# RedBot.net
KiCad netlist of a schematic drawn in EAGLE
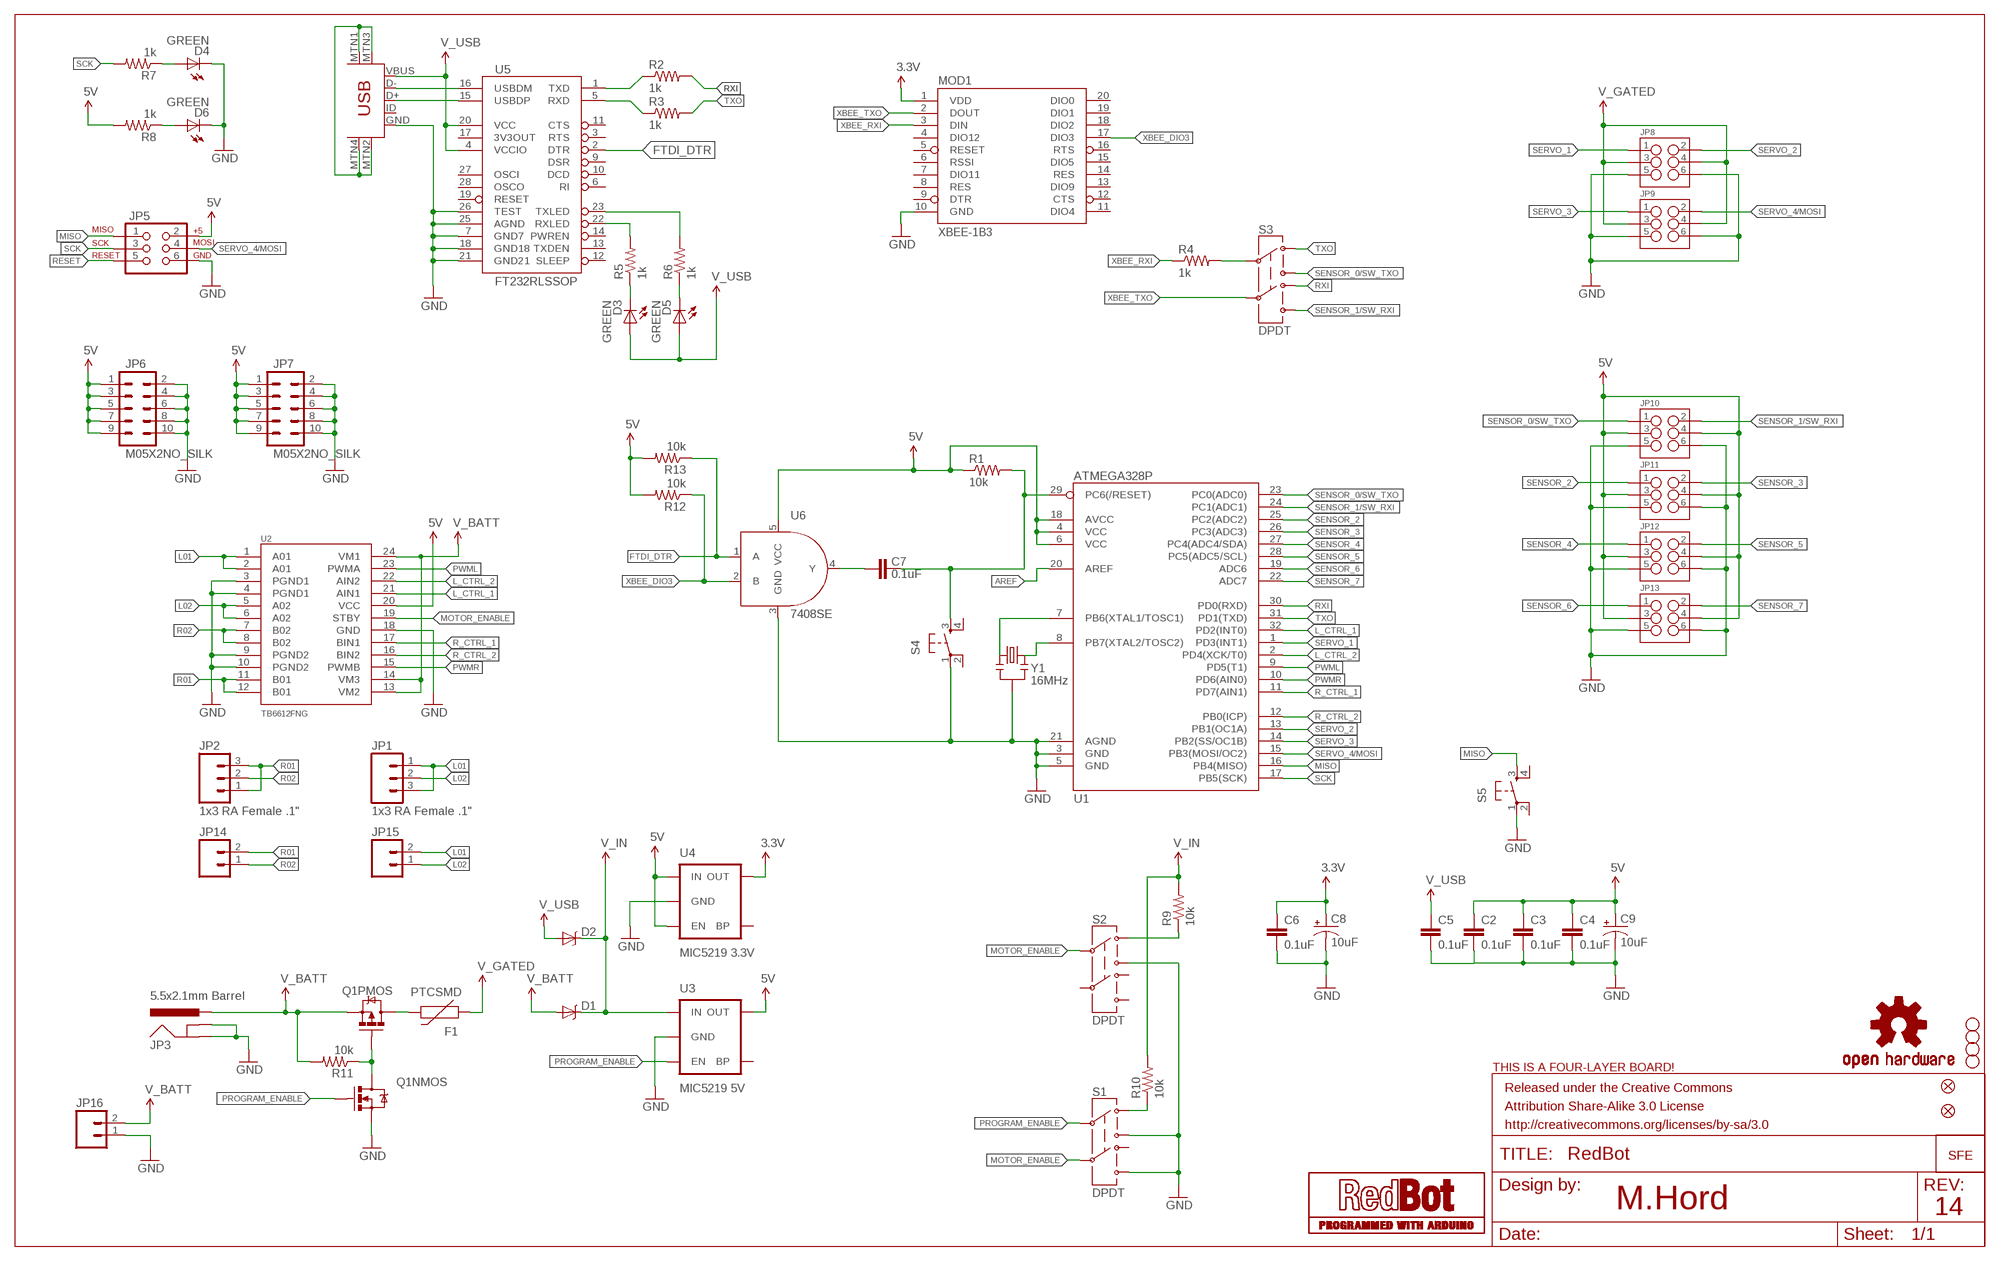
[diagram p0: schematic, sheet 1]

(export (version "E")
  (design (tool "Eeschema 10.0.6"))
  (components
    (comp (ref "C2")
      (value "0.1uF")
      (footprint "eagle-import:0603-CAP")
      (libsource (lib "eagle-import") (part "0.1UF-25V(+80/-20%)(0603)"))
    )
    (comp (ref "C3")
      (value "0.1uF")
      (footprint "eagle-import:0603-CAP")
      (libsource (lib "eagle-import") (part "0.1UF-25V(+80/-20%)(0603)"))
    )
    (comp (ref "C4")
      (value "0.1uF")
      (footprint "eagle-import:0603-CAP")
      (libsource (lib "eagle-import") (part "0.1UF-25V(+80/-20%)(0603)"))
    )
    (comp (ref "C5")
      (value "0.1uF")
      (footprint "eagle-import:0603-CAP")
      (libsource (lib "eagle-import") (part "0.1UF-25V(+80/-20%)(0603)"))
    )
    (comp (ref "C6")
      (value "0.1uF")
      (footprint "eagle-import:0603-CAP")
      (libsource (lib "eagle-import") (part "0.1UF-25V(+80/-20%)(0603)"))
    )
    (comp (ref "C7")
      (value "0.1uF")
      (footprint "eagle-import:0603-CAP")
      (fields (field (name "PROD_ID") "CAP-00810"))
      (libsource (lib "eagle-import") (part "0.1UF-25V(+80/-20%)(0603)"))
    )
    (comp (ref "C8")
      (value "10uF")
      (footprint "eagle-import:EIA3216")
      (libsource (lib "eagle-import") (part "10UF-16V-10%(TANT)"))
    )
    (comp (ref "C9")
      (value "10uF")
      (footprint "eagle-import:EIA3216")
      (libsource (lib "eagle-import") (part "10UF-16V-10%(TANT)"))
    )
    (comp (ref "D1")
      (value "B340A")
      (footprint "eagle-import:SMA-DIODE")
      (libsource (lib "eagle-import") (part "B340A"))
    )
    (comp (ref "D2")
      (value "B340A")
      (footprint "eagle-import:SMA-DIODE")
      (libsource (lib "eagle-import") (part "B340A"))
    )
    (comp (ref "D3")
      (value "GREEN")
      (footprint "eagle-import:LED-0603")
      (libsource (lib "eagle-import") (part "LED-GREEN0603"))
    )
    (comp (ref "D4")
      (value "GREEN")
      (footprint "eagle-import:LED-0603")
      (libsource (lib "eagle-import") (part "LED-GREEN0603"))
    )
    (comp (ref "D5")
      (value "GREEN")
      (footprint "eagle-import:LED-0603")
      (fields (field (name "PROD_ID") "DIO-00821"))
      (libsource (lib "eagle-import") (part "LED-GREEN0603"))
    )
    (comp (ref "D6")
      (value "GREEN")
      (footprint "eagle-import:LED-0603")
      (libsource (lib "eagle-import") (part "LED-GREEN0603"))
    )
    (comp (ref "F1")
      (value "PTCSMD")
      (footprint "eagle-import:PTC-1206")
      (libsource (lib "eagle-import") (part "PTCSMD"))
    )
    (comp (ref "FID1")
      (value "FIDUCIALUFIDUCIAL")
      (footprint "eagle-import:MICRO-FIDUCIAL")
      (libsource (lib "eagle-import") (part "FIDUCIALUFIDUCIAL"))
    )
    (comp (ref "FID2")
      (value "FIDUCIALUFIDUCIAL")
      (footprint "eagle-import:MICRO-FIDUCIAL")
      (libsource (lib "eagle-import") (part "FIDUCIALUFIDUCIAL"))
    )
    (comp (ref "FRAME1")
      (value "FRAME-LETTER")
      (footprint "eagle-import:CREATIVE_COMMONS")
      (libsource (lib "eagle-import") (part "FRAME-LETTER"))
    )
    (comp (ref "JP1")
      (value "1x3 RA Female .1\"")
      (footprint "eagle-import:1X03_SMD_RA_FEMALE")
      (libsource (lib "eagle-import") (part "M03SMD_RA_FEMALE"))
    )
    (comp (ref "JP2")
      (value "1x3 RA Female .1\"")
      (footprint "eagle-import:1X03_SMD_RA_FEMALE")
      (libsource (lib "eagle-import") (part "M03SMD_RA_FEMALE"))
    )
    (comp (ref "JP3")
      (value "5.5x2.1mm Barrel")
      (footprint "eagle-import:POWER_JACK_SMD")
      (libsource (lib "eagle-import") (part "POWER_JACKSMD"))
    )
    (comp (ref "JP4")
      (value "USB-B")
      (footprint "eagle-import:USB-MINIB")
      (libsource (lib "eagle-import") (part "USB-MINIB-5PIN"))
    )
    (comp (ref "JP5")
      (value "AVR_SPI_PRG_6PTH")
      (footprint "eagle-import:2X3")
      (libsource (lib "eagle-import") (part "AVR_SPI_PRG_6PTH"))
    )
    (comp (ref "JP6")
      (value "M05X2NO_SILK")
      (footprint "eagle-import:2X5_NOSILK")
      (libsource (lib "eagle-import") (part "M05X2NO_SILK"))
    )
    (comp (ref "JP7")
      (value "M05X2NO_SILK")
      (footprint "eagle-import:2X5_NOSILK")
      (libsource (lib "eagle-import") (part "M05X2NO_SILK"))
    )
    (comp (ref "JP8")
      (value "M03X2SMT")
      (footprint "eagle-import:2X3_SMT_POSTS")
      (libsource (lib "eagle-import") (part "M03X2SMT"))
    )
    (comp (ref "JP9")
      (value "M03X2SMT")
      (footprint "eagle-import:2X3_SMT_POSTS")
      (libsource (lib "eagle-import") (part "M03X2SMT"))
    )
    (comp (ref "JP10")
      (value "M03X2SMT")
      (footprint "eagle-import:2X3_SMT_POSTS")
      (libsource (lib "eagle-import") (part "M03X2SMT"))
    )
    (comp (ref "JP11")
      (value "M03X2SMT")
      (footprint "eagle-import:2X3_SMT_POSTS")
      (libsource (lib "eagle-import") (part "M03X2SMT"))
    )
    (comp (ref "JP12")
      (value "M03X2SMT")
      (footprint "eagle-import:2X3_SMT_POSTS")
      (libsource (lib "eagle-import") (part "M03X2SMT"))
    )
    (comp (ref "JP13")
      (value "M03X2SMT")
      (footprint "eagle-import:2X3_SMT_POSTS")
      (libsource (lib "eagle-import") (part "M03X2SMT"))
    )
    (comp (ref "JP14")
      (value "M02PTH")
      (footprint "eagle-import:1X02")
      (libsource (lib "eagle-import") (part "M02PTH"))
    )
    (comp (ref "JP15")
      (value "M02PTH")
      (footprint "eagle-import:1X02")
      (libsource (lib "eagle-import") (part "M02PTH"))
    )
    (comp (ref "JP16")
      (value "M02PTH")
      (footprint "eagle-import:1X02")
      (libsource (lib "eagle-import") (part "M02PTH"))
    )
    (comp (ref "MOD1")
      (value "XBEE-1B3")
      (footprint "eagle-import:XBEE-SMD")
      (libsource (lib "eagle-import") (part "XBEE-1B3"))
    )
    (comp (ref "Q1")
      (value "IRF7509")
      (footprint "eagle-import:MSOP8")
      (libsource (lib "eagle-import") (part "IRF7509"))
    )
    (comp (ref "R1")
      (value "10k")
      (footprint "eagle-import:0603-RES")
      (libsource (lib "eagle-import") (part "10KOHM1/10W1%(0603)0603"))
    )
    (comp (ref "R2")
      (value "1k")
      (footprint "eagle-import:0603-RES")
      (libsource (lib "eagle-import") (part "1K-1%"))
    )
    (comp (ref "R3")
      (value "1k")
      (footprint "eagle-import:0603-RES")
      (libsource (lib "eagle-import") (part "1K-1%"))
    )
    (comp (ref "R4")
      (value "1k")
      (footprint "eagle-import:0603-RES")
      (fields (field (name "PROD_ID") "RES-07856"))
      (libsource (lib "eagle-import") (part "1K-1%"))
    )
    (comp (ref "R5")
      (value "1k")
      (footprint "eagle-import:0603-RES")
      (fields (field (name "PROD_ID") "RES-07856"))
      (libsource (lib "eagle-import") (part "1K-1%"))
    )
    (comp (ref "R6")
      (value "1k")
      (footprint "eagle-import:0603-RES")
      (fields (field (name "PROD_ID") "RES-07856"))
      (libsource (lib "eagle-import") (part "1K-1%"))
    )
    (comp (ref "R7")
      (value "1k")
      (footprint "eagle-import:0603-RES")
      (fields (field (name "PROD_ID") "RES-07856"))
      (libsource (lib "eagle-import") (part "1K-1%"))
    )
    (comp (ref "R8")
      (value "1k")
      (footprint "eagle-import:0603-RES")
      (fields (field (name "PROD_ID") "RES-07856"))
      (libsource (lib "eagle-import") (part "1K-1%"))
    )
    (comp (ref "R9")
      (value "10k")
      (footprint "eagle-import:0603-RES")
      (fields (field (name "PROD_ID") "RES-00824"))
      (libsource (lib "eagle-import") (part "10KOHM1/10W1%(0603)0603"))
    )
    (comp (ref "R10")
      (value "10k")
      (footprint "eagle-import:0603-RES")
      (fields (field (name "PROD_ID") "RES-00824"))
      (libsource (lib "eagle-import") (part "10KOHM1/10W1%(0603)0603"))
    )
    (comp (ref "R11")
      (value "10k")
      (footprint "eagle-import:0603-RES")
      (fields (field (name "PROD_ID") "RES-00824"))
      (libsource (lib "eagle-import") (part "10KOHM1/10W1%(0603)0603"))
    )
    (comp (ref "R12")
      (value "10k")
      (footprint "eagle-import:0603-RES")
      (fields (field (name "PROD_ID") "RES-00824"))
      (libsource (lib "eagle-import") (part "10KOHM1/10W1%(0603)0603"))
    )
    (comp (ref "R13")
      (value "10k")
      (footprint "eagle-import:0603-RES")
      (fields (field (name "PROD_ID") "RES-00824"))
      (libsource (lib "eagle-import") (part "10KOHM1/10W1%(0603)0603"))
    )
    (comp (ref "S1")
      (value "DPDT")
      (footprint "eagle-import:AYZ0202")
      (libsource (lib "eagle-import") (part "SWITCH-DPDTAYZ0202"))
    )
    (comp (ref "S2")
      (value "DPDT")
      (footprint "eagle-import:AYZ0202")
      (libsource (lib "eagle-import") (part "SWITCH-DPDTAYZ0202"))
    )
    (comp (ref "S3")
      (value "DPDT")
      (footprint "eagle-import:AYZ0202")
      (fields (field (name "PROD_ID") "SWCH-08179"))
      (libsource (lib "eagle-import") (part "SWITCH-DPDTAYZ0202"))
    )
    (comp (ref "S4")
      (value "TAC_SWITCHSMD")
      (footprint "eagle-import:TACTILE_SWITCH_SMD")
      (libsource (lib "eagle-import") (part "TAC_SWITCHSMD"))
    )
    (comp (ref "S5")
      (value "TAC_SWITCHSMD")
      (footprint "eagle-import:TACTILE_SWITCH_SMD")
      (libsource (lib "eagle-import") (part "TAC_SWITCHSMD"))
    )
    (comp (ref "SFE-LOGO1")
      (value "LOGO-SFENEW")
      (footprint "eagle-import:SFE-NEW-WEBLOGO")
      (libsource (lib "eagle-import") (part "LOGO-SFENEW"))
    )
    (comp (ref "STANDOFF1")
      (value "STAND-OFF")
      (footprint "eagle-import:STAND-OFF")
      (libsource (lib "eagle-import") (part "STAND-OFF"))
    )
    (comp (ref "STANDOFF2")
      (value "STAND-OFF")
      (footprint "eagle-import:STAND-OFF")
      (libsource (lib "eagle-import") (part "STAND-OFF"))
    )
    (comp (ref "STANDOFF3")
      (value "STAND-OFF")
      (footprint "eagle-import:STAND-OFF")
      (libsource (lib "eagle-import") (part "STAND-OFF"))
    )
    (comp (ref "STANDOFF4")
      (value "STAND-OFF")
      (footprint "eagle-import:STAND-OFF")
      (libsource (lib "eagle-import") (part "STAND-OFF"))
    )
    (comp (ref "U$17")
      (value "OSHW-LOGOS")
      (footprint "eagle-import:OSHW-LOGO-S")
      (libsource (lib "eagle-import") (part "OSHW-LOGOS"))
    )
    (comp (ref "U$21")
      (value "FOUR_LAYER_WARNING")
      (footprint "eagle-import:FOUR_LAYER_WARNING")
      (libsource (lib "eagle-import") (part "FOUR_LAYER_WARNING"))
    )
    (comp (ref "U$23")
      (value "REDBOT_LOGO")
      (footprint "eagle-import:REDBOT_LOGO")
      (libsource (lib "eagle-import") (part "REDBOT_LOGO"))
    )
    (comp (ref "U1")
      (value "ATMEGA328P")
      (footprint "eagle-import:TQFP32-08")
      (libsource (lib "eagle-import") (part "ATMEGA328_SMT"))
    )
    (comp (ref "U2")
      (value "TB6612FNG")
      (footprint "eagle-import:SSOP24")
      (libsource (lib "eagle-import") (part "TB6621FNG"))
    )
    (comp (ref "U3")
      (value "MIC5219 5V")
      (footprint "eagle-import:SOT23-5")
      (fields (field (name "PROD_ID") "VREG-10107"))
      (libsource (lib "eagle-import") (part "V_REG_MIC52195V"))
    )
    (comp (ref "U4")
      (value "MIC5219 3.3V")
      (footprint "eagle-import:SOT23-5")
      (libsource (lib "eagle-import") (part "V_REG_MIC52193.3V"))
    )
    (comp (ref "U5")
      (value "FT232RLSSOP")
      (footprint "eagle-import:SSOP28DB")
      (libsource (lib "eagle-import") (part "FT232RLSSOP"))
    )
    (comp (ref "U6")
      (value "7408SE")
      (footprint "eagle-import:SOT353")
      (libsource (lib "eagle-import") (part "7408SE"))
    )
    (comp (ref "Y1")
      (value "16MHz")
      (footprint "eagle-import:RESONATOR-SMD")
      (libsource (lib "eagle-import") (part "RESONATOR16MHZ"))
    )
  )
  (nets
    (net (code "1") (name "3.3V") (class "Default")
      (node (ref "C6") (pin "1") (pinfunction "1_1") (pintype "passive"))
      (node (ref "C8") (pin "A") (pinfunction "+_A") (pintype "passive"))
      (node (ref "MOD1") (pin "1") (pinfunction "VDD_1") (pintype "power_in"))
      (node (ref "U4") (pin "5") (pinfunction "OUT_5") (pintype "passive"))
    )
    (net (code "2") (name "5V") (class "Default")
      (node (ref "C2") (pin "1") (pinfunction "1_1") (pintype "passive"))
      (node (ref "C3") (pin "1") (pinfunction "1_1") (pintype "passive"))
      (node (ref "C4") (pin "1") (pinfunction "1_1") (pintype "passive"))
      (node (ref "C9") (pin "A") (pinfunction "+_A") (pintype "passive"))
      (node (ref "JP10") (pin "3") (pinfunction "3_3") (pintype "bidirectional"))
      (node (ref "JP10") (pin "4") (pinfunction "4_4") (pintype "bidirectional"))
      (node (ref "JP11") (pin "3") (pinfunction "3_3") (pintype "bidirectional"))
      (node (ref "JP11") (pin "4") (pinfunction "4_4") (pintype "bidirectional"))
      (node (ref "JP12") (pin "3") (pinfunction "3_3") (pintype "bidirectional"))
      (node (ref "JP12") (pin "4") (pinfunction "4_4") (pintype "bidirectional"))
      (node (ref "JP13") (pin "3") (pinfunction "3_3") (pintype "bidirectional"))
      (node (ref "JP13") (pin "4") (pinfunction "4_4") (pintype "bidirectional"))
      (node (ref "JP5") (pin "2") (pinfunction "2_2") (pintype "passive"))
      (node (ref "JP6") (pin "1") (pinfunction "1_1") (pintype "passive"))
      (node (ref "JP6") (pin "3") (pinfunction "3_3") (pintype "passive"))
      (node (ref "JP6") (pin "5") (pinfunction "5_5") (pintype "passive"))
      (node (ref "JP6") (pin "7") (pinfunction "7_7") (pintype "passive"))
      (node (ref "JP6") (pin "9") (pinfunction "9_9") (pintype "passive"))
      (node (ref "JP7") (pin "1") (pinfunction "1_1") (pintype "passive"))
      (node (ref "JP7") (pin "3") (pinfunction "3_3") (pintype "passive"))
      (node (ref "JP7") (pin "5") (pinfunction "5_5") (pintype "passive"))
      (node (ref "JP7") (pin "7") (pinfunction "7_7") (pintype "passive"))
      (node (ref "JP7") (pin "9") (pinfunction "9_9") (pintype "passive"))
      (node (ref "R1") (pin "1") (pinfunction "1_1") (pintype "passive"))
      (node (ref "R12") (pin "2") (pinfunction "2_2") (pintype "passive"))
      (node (ref "R13") (pin "2") (pinfunction "2_2") (pintype "passive"))
      (node (ref "R8") (pin "2") (pinfunction "2_2") (pintype "passive"))
      (node (ref "U1") (pin "18") (pinfunction "AVCC_18") (pintype "bidirectional"))
      (node (ref "U1") (pin "4") (pinfunction "VCC_4") (pintype "bidirectional"))
      (node (ref "U1") (pin "6") (pinfunction "VCC_6") (pintype "bidirectional"))
      (node (ref "U2") (pin "20") (pinfunction "VCC_20") (pintype "bidirectional"))
      (node (ref "U3") (pin "5") (pinfunction "OUT_5") (pintype "passive"))
      (node (ref "U4") (pin "1") (pinfunction "IN_1") (pintype "input"))
      (node (ref "U4") (pin "3") (pinfunction "EN_3") (pintype "input"))
      (node (ref "U6") (pin "5") (pinfunction "VCC_5") (pintype "bidirectional"))
    )
    (net (code "3") (name "AREF") (class "Default")
      (node (ref "U1") (pin "20") (pinfunction "AREF_20") (pintype "bidirectional"))
    )
    (net (code "4") (name "FTDI_DTR") (class "Default")
      (node (ref "R13") (pin "1") (pinfunction "1_1") (pintype "passive"))
      (node (ref "U5") (pin "2") (pinfunction "DTR_2") (pintype "output"))
      (node (ref "U6") (pin "1") (pinfunction "A_1") (pintype "bidirectional"))
    )
    (net (code "5") (name "GND") (class "Default")
      (node (ref "C2") (pin "2") (pinfunction "2_2") (pintype "passive"))
      (node (ref "C3") (pin "2") (pinfunction "2_2") (pintype "passive"))
      (node (ref "C4") (pin "2") (pinfunction "2_2") (pintype "passive"))
      (node (ref "C5") (pin "2") (pinfunction "2_2") (pintype "passive"))
      (node (ref "C6") (pin "2") (pinfunction "2_2") (pintype "passive"))
      (node (ref "C8") (pin "C") (pinfunction "-_C") (pintype "passive"))
      (node (ref "C9") (pin "C") (pinfunction "-_C") (pintype "passive"))
      (node (ref "D4") (pin "C") (pinfunction "C_C") (pintype "passive"))
      (node (ref "D6") (pin "C") (pinfunction "C_C") (pintype "passive"))
      (node (ref "JP10") (pin "5") (pinfunction "5_5") (pintype "bidirectional"))
      (node (ref "JP10") (pin "6") (pinfunction "6_6") (pintype "bidirectional"))
      (node (ref "JP11") (pin "5") (pinfunction "5_5") (pintype "bidirectional"))
      (node (ref "JP11") (pin "6") (pinfunction "6_6") (pintype "bidirectional"))
      (node (ref "JP12") (pin "5") (pinfunction "5_5") (pintype "bidirectional"))
      (node (ref "JP12") (pin "6") (pinfunction "6_6") (pintype "bidirectional"))
      (node (ref "JP13") (pin "5") (pinfunction "5_5") (pintype "bidirectional"))
      (node (ref "JP13") (pin "6") (pinfunction "6_6") (pintype "bidirectional"))
      (node (ref "JP16") (pin "1") (pinfunction "1_1") (pintype "passive"))
      (node (ref "JP3") (pin "GND") (pinfunction "GNDBREAK_GND") (pintype "bidirectional"))
      (node (ref "JP3") (pin "P$4") (pinfunction "GND_P$4") (pintype "bidirectional"))
      (node (ref "JP4") (pin "GND") (pinfunction "GND_GND") (pintype "bidirectional"))
      (node (ref "JP5") (pin "6") (pinfunction "6_6") (pintype "passive"))
      (node (ref "JP6") (pin "10") (pinfunction "10_10") (pintype "passive"))
      (node (ref "JP6") (pin "2") (pinfunction "2_2") (pintype "passive"))
      (node (ref "JP6") (pin "4") (pinfunction "4_4") (pintype "passive"))
      (node (ref "JP6") (pin "6") (pinfunction "6_6") (pintype "passive"))
      (node (ref "JP6") (pin "8") (pinfunction "8_8") (pintype "passive"))
      (node (ref "JP7") (pin "10") (pinfunction "10_10") (pintype "passive"))
      (node (ref "JP7") (pin "2") (pinfunction "2_2") (pintype "passive"))
      (node (ref "JP7") (pin "4") (pinfunction "4_4") (pintype "passive"))
      (node (ref "JP7") (pin "6") (pinfunction "6_6") (pintype "passive"))
      (node (ref "JP7") (pin "8") (pinfunction "8_8") (pintype "passive"))
      (node (ref "JP8") (pin "5") (pinfunction "5_5") (pintype "bidirectional"))
      (node (ref "JP8") (pin "6") (pinfunction "6_6") (pintype "bidirectional"))
      (node (ref "JP9") (pin "5") (pinfunction "5_5") (pintype "bidirectional"))
      (node (ref "JP9") (pin "6") (pinfunction "6_6") (pintype "bidirectional"))
      (node (ref "MOD1") (pin "10") (pinfunction "GND_10") (pintype "power_in"))
      (node (ref "Q1") (pin "1") (pinfunction "S_1") (pintype "passive"))
      (node (ref "S1") (pin "3") (pinfunction "3_3") (pintype "bidirectional"))
      (node (ref "S1") (pin "6") (pinfunction "6_6") (pintype "bidirectional"))
      (node (ref "S2") (pin "3") (pinfunction "3_3") (pintype "bidirectional"))
      (node (ref "S4") (pin "1") (pinfunction "1_1") (pintype "passive"))
      (node (ref "S5") (pin "1") (pinfunction "1_1") (pintype "passive"))
      (node (ref "U1") (pin "21") (pinfunction "AGND_21") (pintype "bidirectional"))
      (node (ref "U1") (pin "3") (pinfunction "GND_3") (pintype "bidirectional"))
      (node (ref "U1") (pin "5") (pinfunction "GND_5") (pintype "bidirectional"))
      (node (ref "U2") (pin "10") (pinfunction "PGND2_10") (pintype "bidirectional"))
      (node (ref "U2") (pin "18") (pinfunction "GND_18") (pintype "bidirectional"))
      (node (ref "U2") (pin "3") (pinfunction "PGND1_3") (pintype "bidirectional"))
      (node (ref "U2") (pin "4") (pinfunction "PGND1_4") (pintype "bidirectional"))
      (node (ref "U2") (pin "9") (pinfunction "PGND2_9") (pintype "bidirectional"))
      (node (ref "U3") (pin "2") (pinfunction "GND_2") (pintype "input"))
      (node (ref "U4") (pin "2") (pinfunction "GND_2") (pintype "input"))
      (node (ref "U5") (pin "18") (pinfunction "GND18_18") (pintype "power_in"))
      (node (ref "U5") (pin "21") (pinfunction "GND21_21") (pintype "power_in"))
      (node (ref "U5") (pin "25") (pinfunction "AGND_25") (pintype "power_in"))
      (node (ref "U5") (pin "26") (pinfunction "TEST_26") (pintype "input"))
      (node (ref "U5") (pin "7") (pinfunction "GND7_7") (pintype "power_in"))
      (node (ref "U6") (pin "3") (pinfunction "GND_3") (pintype "bidirectional"))
      (node (ref "Y1") (pin "2") (pinfunction "2_2") (pintype "passive"))
    )
    (net (code "6") (name "L01") (class "Default")
      (node (ref "JP1") (pin "1") (pinfunction "1_1") (pintype "passive"))
      (node (ref "JP1") (pin "3") (pinfunction "3_3") (pintype "passive"))
      (node (ref "JP15") (pin "2") (pinfunction "2_2") (pintype "passive"))
      (node (ref "U2") (pin "1") (pinfunction "A01_1") (pintype "bidirectional"))
      (node (ref "U2") (pin "2") (pinfunction "A01_2") (pintype "bidirectional"))
    )
    (net (code "7") (name "L02") (class "Default")
      (node (ref "JP1") (pin "2") (pinfunction "2_2") (pintype "passive"))
      (node (ref "JP15") (pin "1") (pinfunction "1_1") (pintype "passive"))
      (node (ref "U2") (pin "5") (pinfunction "A02_5") (pintype "bidirectional"))
      (node (ref "U2") (pin "6") (pinfunction "A02_6") (pintype "bidirectional"))
    )
    (net (code "8") (name "L_CTRL_1") (class "Default")
      (node (ref "U1") (pin "32") (pinfunction "PD2(INT0)_32") (pintype "bidirectional"))
      (node (ref "U2") (pin "21") (pinfunction "AIN1_21") (pintype "bidirectional"))
    )
    (net (code "9") (name "L_CTRL_2") (class "Default")
      (node (ref "U1") (pin "2") (pinfunction "PD4(XCK/T0)_2") (pintype "bidirectional"))
      (node (ref "U2") (pin "22") (pinfunction "AIN2_22") (pintype "bidirectional"))
    )
    (net (code "10") (name "MISO") (class "Default")
      (node (ref "JP5") (pin "1") (pinfunction "1_1") (pintype "passive"))
      (node (ref "S5") (pin "3") (pinfunction "3_3") (pintype "passive"))
      (node (ref "U1") (pin "16") (pinfunction "PB4(MISO)_16") (pintype "bidirectional"))
    )
    (net (code "11") (name "MOTOR_ENABLE") (class "Default")
      (node (ref "S1") (pin "5") (pinfunction "5_5") (pintype "bidirectional"))
      (node (ref "S2") (pin "2") (pinfunction "2_2") (pintype "bidirectional"))
      (node (ref "U2") (pin "19") (pinfunction "STBY_19") (pintype "bidirectional"))
    )
    (net (code "12") (name "Net-(D3-PadC)") (class "Default")
      (node (ref "D3") (pin "C") (pinfunction "C_C") (pintype "passive"))
      (node (ref "R5") (pin "1") (pinfunction "1_1") (pintype "passive"))
    )
    (net (code "13") (name "Net-(D4-PadA)") (class "Default")
      (node (ref "D4") (pin "A") (pinfunction "A_A") (pintype "passive"))
      (node (ref "R7") (pin "1") (pinfunction "1_1") (pintype "passive"))
    )
    (net (code "14") (name "Net-(D5-PadC)") (class "Default")
      (node (ref "D5") (pin "C") (pinfunction "C_C") (pintype "passive"))
      (node (ref "R6") (pin "1") (pinfunction "1_1") (pintype "passive"))
    )
    (net (code "15") (name "Net-(D6-PadA)") (class "Default")
      (node (ref "D6") (pin "A") (pinfunction "A_A") (pintype "passive"))
      (node (ref "R8") (pin "1") (pinfunction "1_1") (pintype "passive"))
    )
    (net (code "16") (name "Net-(F1-Pad2)") (class "Default")
      (node (ref "F1") (pin "2") (pinfunction "2_2") (pintype "bidirectional"))
      (node (ref "Q1") (pin "5") (pinfunction "D_5") (pintype "passive"))
      (node (ref "Q1") (pin "6") (pinfunction "D_6") (pintype "passive"))
    )
    (net (code "17") (name "Net-(JP4-MTN1)") (class "Default")
      (node (ref "JP4") (pin "MTN1") (pinfunction "MTN2_MTN1") (pintype "bidirectional"))
      (node (ref "JP4") (pin "MTN2") (pinfunction "MTN3_MTN2") (pintype "bidirectional"))
      (node (ref "JP4") (pin "MTN3") (pinfunction "MTN1_MTN3") (pintype "bidirectional"))
      (node (ref "JP4") (pin "MTN4") (pinfunction "MTN4_MTN4") (pintype "bidirectional"))
    )
    (net (code "18") (name "Net-(Q1B-G)") (class "Default")
      (node (ref "Q1") (pin "4") (pinfunction "G_4") (pintype "passive"))
      (node (ref "Q1") (pin "7") (pinfunction "D_7") (pintype "passive"))
      (node (ref "Q1") (pin "8") (pinfunction "D_8") (pintype "passive"))
      (node (ref "R11") (pin "1") (pinfunction "1_1") (pintype "passive"))
    )
    (net (code "19") (name "Net-(R4-Pad2)") (class "Default")
      (node (ref "R4") (pin "2") (pinfunction "2_2") (pintype "passive"))
      (node (ref "S3") (pin "2") (pinfunction "2_2") (pintype "bidirectional"))
    )
    (net (code "20") (name "Net-(R9-Pad1)") (class "Default")
      (node (ref "R9") (pin "1") (pinfunction "1_1") (pintype "passive"))
      (node (ref "S2") (pin "1") (pinfunction "1_1") (pintype "bidirectional"))
    )
    (net (code "21") (name "Net-(R10-Pad1)") (class "Default")
      (node (ref "R10") (pin "1") (pinfunction "1_1") (pintype "passive"))
      (node (ref "S1") (pin "1") (pinfunction "1_1") (pintype "bidirectional"))
    )
    (net (code "22") (name "Net-(U1-PB6(XTAL1{slash}TOSC1))") (class "Default")
      (node (ref "U1") (pin "7") (pinfunction "PB6(XTAL1/TOSC1)_7") (pintype "bidirectional"))
      (node (ref "Y1") (pin "1") (pinfunction "1_1") (pintype "passive"))
    )
    (net (code "23") (name "Net-(U1-PB7(XTAL2{slash}TOSC2))") (class "Default")
      (node (ref "U1") (pin "8") (pinfunction "PB7(XTAL2/TOSC2)_8") (pintype "bidirectional"))
      (node (ref "Y1") (pin "3") (pinfunction "3_3") (pintype "passive"))
    )
    (net (code "24") (name "Net-(U5-RXD)") (class "Default")
      (node (ref "R3") (pin "1") (pinfunction "1_1") (pintype "passive"))
      (node (ref "U5") (pin "5") (pinfunction "RXD_5") (pintype "input"))
    )
    (net (code "25") (name "Net-(U5-RXLED)") (class "Default")
      (node (ref "R5") (pin "2") (pinfunction "2_2") (pintype "passive"))
      (node (ref "U5") (pin "22") (pinfunction "RXLED_22") (pintype "input"))
    )
    (net (code "26") (name "Net-(U5-TXD)") (class "Default")
      (node (ref "R2") (pin "1") (pinfunction "1_1") (pintype "passive"))
      (node (ref "U5") (pin "1") (pinfunction "TXD_1") (pintype "output"))
    )
    (net (code "27") (name "Net-(U5-TXLED)") (class "Default")
      (node (ref "R6") (pin "2") (pinfunction "2_2") (pintype "passive"))
      (node (ref "U5") (pin "23") (pinfunction "TXLED_23") (pintype "input"))
    )
    (net (code "28") (name "Net-(U5-USBDM)") (class "Default")
      (node (ref "JP4") (pin "D-") (pinfunction "D-_D-") (pintype "bidirectional"))
      (node (ref "U5") (pin "16") (pinfunction "USBDM_16") (pintype "bidirectional"))
    )
    (net (code "29") (name "Net-(U5-USBDP)") (class "Default")
      (node (ref "JP4") (pin "D+") (pinfunction "D+_D+") (pintype "bidirectional"))
      (node (ref "U5") (pin "15") (pinfunction "USBDP_15") (pintype "bidirectional"))
    )
    (net (code "30") (name "Net-(U6-Y)") (class "Default")
      (node (ref "C7") (pin "2") (pinfunction "2_2") (pintype "passive"))
      (node (ref "U6") (pin "4") (pinfunction "Y_4") (pintype "bidirectional"))
    )
    (net (code "31") (name "PROGRAM_ENABLE") (class "Default")
      (node (ref "Q1") (pin "2") (pinfunction "G_2") (pintype "passive"))
      (node (ref "S1") (pin "2") (pinfunction "2_2") (pintype "bidirectional"))
      (node (ref "U3") (pin "3") (pinfunction "EN_3") (pintype "input"))
    )
    (net (code "32") (name "PWML") (class "Default")
      (node (ref "U1") (pin "9") (pinfunction "PD5(T1)_9") (pintype "bidirectional"))
      (node (ref "U2") (pin "23") (pinfunction "PWMA_23") (pintype "bidirectional"))
    )
    (net (code "33") (name "PWMR") (class "Default")
      (node (ref "U1") (pin "10") (pinfunction "PD6(AIN0)_10") (pintype "bidirectional"))
      (node (ref "U2") (pin "15") (pinfunction "PWMB_15") (pintype "bidirectional"))
    )
    (net (code "34") (name "R01") (class "Default")
      (node (ref "JP14") (pin "2") (pinfunction "2_2") (pintype "passive"))
      (node (ref "JP2") (pin "1") (pinfunction "1_1") (pintype "passive"))
      (node (ref "JP2") (pin "3") (pinfunction "3_3") (pintype "passive"))
      (node (ref "U2") (pin "11") (pinfunction "B01_11") (pintype "bidirectional"))
      (node (ref "U2") (pin "12") (pinfunction "B01_12") (pintype "bidirectional"))
    )
    (net (code "35") (name "R02") (class "Default")
      (node (ref "JP14") (pin "1") (pinfunction "1_1") (pintype "passive"))
      (node (ref "JP2") (pin "2") (pinfunction "2_2") (pintype "passive"))
      (node (ref "U2") (pin "7") (pinfunction "B02_7") (pintype "bidirectional"))
      (node (ref "U2") (pin "8") (pinfunction "B02_8") (pintype "bidirectional"))
    )
    (net (code "36") (name "RESET") (class "Default")
      (node (ref "C7") (pin "1") (pinfunction "1_1") (pintype "passive"))
      (node (ref "JP5") (pin "5") (pinfunction "5_5") (pintype "passive"))
      (node (ref "R1") (pin "2") (pinfunction "2_2") (pintype "passive"))
      (node (ref "S4") (pin "3") (pinfunction "3_3") (pintype "passive"))
      (node (ref "U1") (pin "29") (pinfunction "PC6(/RESET)_29") (pintype "bidirectional"))
    )
    (net (code "37") (name "RXI") (class "Default")
      (node (ref "R2") (pin "2") (pinfunction "2_2") (pintype "passive"))
      (node (ref "S3") (pin "4") (pinfunction "4_4") (pintype "bidirectional"))
      (node (ref "U1") (pin "30") (pinfunction "PD0(RXD)_30") (pintype "bidirectional"))
    )
    (net (code "38") (name "R_CTRL_1") (class "Default")
      (node (ref "U1") (pin "11") (pinfunction "PD7(AIN1)_11") (pintype "bidirectional"))
      (node (ref "U2") (pin "17") (pinfunction "BIN1_17") (pintype "bidirectional"))
    )
    (net (code "39") (name "R_CTRL_2") (class "Default")
      (node (ref "U1") (pin "12") (pinfunction "PB0(ICP)_12") (pintype "bidirectional"))
      (node (ref "U2") (pin "16") (pinfunction "BIN2_16") (pintype "bidirectional"))
    )
    (net (code "40") (name "SCK") (class "Default")
      (node (ref "JP5") (pin "3") (pinfunction "3_3") (pintype "passive"))
      (node (ref "R7") (pin "2") (pinfunction "2_2") (pintype "passive"))
      (node (ref "U1") (pin "17") (pinfunction "PB5(SCK)_17") (pintype "bidirectional"))
    )
    (net (code "41") (name "SENSOR_0{slash}SW_TXO") (class "Default")
      (node (ref "JP10") (pin "1") (pinfunction "1_1") (pintype "bidirectional"))
      (node (ref "S3") (pin "3") (pinfunction "3_3") (pintype "bidirectional"))
      (node (ref "U1") (pin "23") (pinfunction "PC0(ADC0)_23") (pintype "bidirectional"))
    )
    (net (code "42") (name "SENSOR_1{slash}SW_RXI") (class "Default")
      (node (ref "JP10") (pin "2") (pinfunction "2_2") (pintype "bidirectional"))
      (node (ref "S3") (pin "6") (pinfunction "6_6") (pintype "bidirectional"))
      (node (ref "U1") (pin "24") (pinfunction "PC1(ADC1)_24") (pintype "bidirectional"))
    )
    (net (code "43") (name "SENSOR_2") (class "Default")
      (node (ref "JP11") (pin "1") (pinfunction "1_1") (pintype "bidirectional"))
      (node (ref "U1") (pin "25") (pinfunction "PC2(ADC2)_25") (pintype "bidirectional"))
    )
    (net (code "44") (name "SENSOR_3") (class "Default")
      (node (ref "JP11") (pin "2") (pinfunction "2_2") (pintype "bidirectional"))
      (node (ref "U1") (pin "26") (pinfunction "PC3(ADC3)_26") (pintype "bidirectional"))
    )
    (net (code "45") (name "SENSOR_4") (class "Default")
      (node (ref "JP12") (pin "1") (pinfunction "1_1") (pintype "bidirectional"))
      (node (ref "U1") (pin "27") (pinfunction "PC4(ADC4/SDA)_27") (pintype "bidirectional"))
    )
    (net (code "46") (name "SENSOR_5") (class "Default")
      (node (ref "JP12") (pin "2") (pinfunction "2_2") (pintype "bidirectional"))
      (node (ref "U1") (pin "28") (pinfunction "PC5(ADC5/SCL)_28") (pintype "bidirectional"))
    )
    (net (code "47") (name "SENSOR_6") (class "Default")
      (node (ref "JP13") (pin "1") (pinfunction "1_1") (pintype "bidirectional"))
      (node (ref "U1") (pin "19") (pinfunction "ADC6_19") (pintype "bidirectional"))
    )
    (net (code "48") (name "SENSOR_7") (class "Default")
      (node (ref "JP13") (pin "2") (pinfunction "2_2") (pintype "bidirectional"))
      (node (ref "U1") (pin "22") (pinfunction "ADC7_22") (pintype "bidirectional"))
    )
    (net (code "49") (name "SERVO_1") (class "Default")
      (node (ref "JP8") (pin "1") (pinfunction "1_1") (pintype "bidirectional"))
      (node (ref "U1") (pin "1") (pinfunction "PD3(INT1)_1") (pintype "bidirectional"))
    )
    (net (code "50") (name "SERVO_2") (class "Default")
      (node (ref "JP8") (pin "2") (pinfunction "2_2") (pintype "bidirectional"))
      (node (ref "U1") (pin "13") (pinfunction "PB1(OC1A)_13") (pintype "bidirectional"))
    )
    (net (code "51") (name "SERVO_3") (class "Default")
      (node (ref "JP9") (pin "1") (pinfunction "1_1") (pintype "bidirectional"))
      (node (ref "U1") (pin "14") (pinfunction "PB2(SS/OC1B)_14") (pintype "bidirectional"))
    )
    (net (code "52") (name "SERVO_4{slash}MOSI") (class "Default")
      (node (ref "JP5") (pin "4") (pinfunction "4_4") (pintype "passive"))
      (node (ref "JP9") (pin "2") (pinfunction "2_2") (pintype "bidirectional"))
      (node (ref "U1") (pin "15") (pinfunction "PB3(MOSI/OC2)_15") (pintype "bidirectional"))
    )
    (net (code "53") (name "TXO") (class "Default")
      (node (ref "R3") (pin "2") (pinfunction "2_2") (pintype "passive"))
      (node (ref "S3") (pin "1") (pinfunction "1_1") (pintype "bidirectional"))
      (node (ref "U1") (pin "31") (pinfunction "PD1(TXD)_31") (pintype "bidirectional"))
    )
    (net (code "54") (name "V_BATT") (class "Default")
      (node (ref "D1") (pin "A") (pinfunction "A_A") (pintype "passive"))
      (node (ref "JP16") (pin "2") (pinfunction "2_2") (pintype "passive"))
      (node (ref "JP3") (pin "VIN0") (pinfunction "PWR_VIN0") (pintype "bidirectional"))
      (node (ref "Q1") (pin "3") (pinfunction "S_3") (pintype "passive"))
      (node (ref "R11") (pin "2") (pinfunction "2_2") (pintype "passive"))
      (node (ref "U2") (pin "13") (pinfunction "VM2_13") (pintype "bidirectional"))
      (node (ref "U2") (pin "14") (pinfunction "VM3_14") (pintype "bidirectional"))
      (node (ref "U2") (pin "24") (pinfunction "VM1_24") (pintype "bidirectional"))
    )
    (net (code "55") (name "V_GATED") (class "Default")
      (node (ref "F1") (pin "1") (pinfunction "1_1") (pintype "bidirectional"))
      (node (ref "JP8") (pin "3") (pinfunction "3_3") (pintype "bidirectional"))
      (node (ref "JP8") (pin "4") (pinfunction "4_4") (pintype "bidirectional"))
      (node (ref "JP9") (pin "3") (pinfunction "3_3") (pintype "bidirectional"))
      (node (ref "JP9") (pin "4") (pinfunction "4_4") (pintype "bidirectional"))
    )
    (net (code "56") (name "V_IN") (class "Default")
      (node (ref "D1") (pin "C") (pinfunction "C_C") (pintype "passive"))
      (node (ref "D2") (pin "C") (pinfunction "C_C") (pintype "passive"))
      (node (ref "R10") (pin "2") (pinfunction "2_2") (pintype "passive"))
      (node (ref "R9") (pin "2") (pinfunction "2_2") (pintype "passive"))
      (node (ref "U3") (pin "1") (pinfunction "IN_1") (pintype "input"))
    )
    (net (code "57") (name "V_USB") (class "Default")
      (node (ref "C5") (pin "1") (pinfunction "1_1") (pintype "passive"))
      (node (ref "D2") (pin "A") (pinfunction "A_A") (pintype "passive"))
      (node (ref "D3") (pin "A") (pinfunction "A_A") (pintype "passive"))
      (node (ref "D5") (pin "A") (pinfunction "A_A") (pintype "passive"))
      (node (ref "JP4") (pin "VBUS") (pinfunction "VBUS_VBUS") (pintype "bidirectional"))
      (node (ref "U5") (pin "20") (pinfunction "VCC_20") (pintype "power_in"))
      (node (ref "U5") (pin "4") (pinfunction "VCCIO_4") (pintype "power_in"))
    )
    (net (code "58") (name "XBEE_DIO3") (class "Default")
      (node (ref "MOD1") (pin "17") (pinfunction "DIO3_17") (pintype "bidirectional"))
      (node (ref "R12") (pin "1") (pinfunction "1_1") (pintype "passive"))
      (node (ref "U6") (pin "2") (pinfunction "B_2") (pintype "bidirectional"))
    )
    (net (code "59") (name "XBEE_RXI") (class "Default")
      (node (ref "MOD1") (pin "3") (pinfunction "DIN_3") (pintype "input"))
      (node (ref "R4") (pin "1") (pinfunction "1_1") (pintype "passive"))
    )
    (net (code "60") (name "XBEE_TXO") (class "Default")
      (node (ref "MOD1") (pin "2") (pinfunction "DOUT_2") (pintype "output"))
      (node (ref "S3") (pin "5") (pinfunction "5_5") (pintype "bidirectional"))
    )
    (net (code "61") (name "unconnected-(JP4-PadID)") (class "Default")
      (node (ref "JP4") (pin "ID") (pinfunction "ID_ID") (pintype "bidirectional"))
    )
    (net (code "62") (name "unconnected-(MOD1-CTS-Pad12)") (class "Default")
      (node (ref "MOD1") (pin "12") (pinfunction "CTS_12") (pintype "output"))
    )
    (net (code "63") (name "unconnected-(MOD1-DIO0-Pad20)") (class "Default")
      (node (ref "MOD1") (pin "20") (pinfunction "DIO0_20") (pintype "bidirectional"))
    )
    (net (code "64") (name "unconnected-(MOD1-DIO1-Pad19)") (class "Default")
      (node (ref "MOD1") (pin "19") (pinfunction "DIO1_19") (pintype "bidirectional"))
    )
    (net (code "65") (name "unconnected-(MOD1-DIO2-Pad18)") (class "Default")
      (node (ref "MOD1") (pin "18") (pinfunction "DIO2_18") (pintype "bidirectional"))
    )
    (net (code "66") (name "unconnected-(MOD1-DIO4-Pad11)") (class "Default")
      (node (ref "MOD1") (pin "11") (pinfunction "DIO4_11") (pintype "bidirectional"))
    )
    (net (code "67") (name "unconnected-(MOD1-DIO5-Pad15)") (class "Default")
      (node (ref "MOD1") (pin "15") (pinfunction "DIO5_15") (pintype "bidirectional"))
    )
    (net (code "68") (name "unconnected-(MOD1-DIO9-Pad13)") (class "Default")
      (node (ref "MOD1") (pin "13") (pinfunction "DIO9_13") (pintype "bidirectional"))
    )
    (net (code "69") (name "unconnected-(MOD1-DIO11-Pad7)") (class "Default")
      (node (ref "MOD1") (pin "7") (pinfunction "DIO11_7") (pintype "bidirectional"))
    )
    (net (code "70") (name "unconnected-(MOD1-DIO12-Pad4)") (class "Default")
      (node (ref "MOD1") (pin "4") (pinfunction "DIO12_4") (pintype "bidirectional"))
    )
    (net (code "71") (name "unconnected-(MOD1-DTR-Pad9)") (class "Default")
      (node (ref "MOD1") (pin "9") (pinfunction "DTR_9") (pintype "bidirectional"))
    )
    (net (code "72") (name "unconnected-(MOD1-RES-Pad8)") (class "Default")
      (node (ref "MOD1") (pin "8") (pinfunction "RES_8") (pintype "bidirectional"))
    )
    (net (code "73") (name "unconnected-(MOD1-RES-Pad14)") (class "Default")
      (node (ref "MOD1") (pin "14") (pinfunction "RES_14") (pintype "bidirectional"))
    )
    (net (code "74") (name "unconnected-(MOD1-RESET-Pad5)") (class "Default")
      (node (ref "MOD1") (pin "5") (pinfunction "RESET_5") (pintype "input"))
    )
    (net (code "75") (name "unconnected-(MOD1-RSSI-Pad6)") (class "Default")
      (node (ref "MOD1") (pin "6") (pinfunction "RSSI_6") (pintype "bidirectional"))
    )
    (net (code "76") (name "unconnected-(MOD1-RTS-Pad16)") (class "Default")
      (node (ref "MOD1") (pin "16") (pinfunction "RTS_16") (pintype "input"))
    )
    (net (code "77") (name "unconnected-(S1-Pad4)") (class "Default")
      (node (ref "S1") (pin "4") (pinfunction "4_4") (pintype "bidirectional"))
    )
    (net (code "78") (name "unconnected-(S2-Pad4)") (class "Default")
      (node (ref "S2") (pin "4") (pinfunction "4_4") (pintype "bidirectional"))
    )
    (net (code "79") (name "unconnected-(S2-Pad5)") (class "Default")
      (node (ref "S2") (pin "5") (pinfunction "5_5") (pintype "bidirectional"))
    )
    (net (code "80") (name "unconnected-(S2-Pad6)") (class "Default")
      (node (ref "S2") (pin "6") (pinfunction "6_6") (pintype "bidirectional"))
    )
    (net (code "81") (name "unconnected-(S4-Pad2)") (class "Default")
      (node (ref "S4") (pin "2") (pinfunction "2_2") (pintype "passive"))
    )
    (net (code "82") (name "unconnected-(S4-Pad4)") (class "Default")
      (node (ref "S4") (pin "4") (pinfunction "4_4") (pintype "passive"))
    )
    (net (code "83") (name "unconnected-(S5-Pad2)") (class "Default")
      (node (ref "S5") (pin "2") (pinfunction "2_2") (pintype "passive"))
    )
    (net (code "84") (name "unconnected-(S5-Pad4)") (class "Default")
      (node (ref "S5") (pin "4") (pinfunction "4_4") (pintype "passive"))
    )
    (net (code "85") (name "unconnected-(U3-BP-Pad4)") (class "Default")
      (node (ref "U3") (pin "4") (pinfunction "BP_4") (pintype "input"))
    )
    (net (code "86") (name "unconnected-(U4-BP-Pad4)") (class "Default")
      (node (ref "U4") (pin "4") (pinfunction "BP_4") (pintype "input"))
    )
    (net (code "87") (name "unconnected-(U5-3V3OUT-Pad17)") (class "Default")
      (node (ref "U5") (pin "17") (pinfunction "3V3OUT_17") (pintype "output"))
    )
    (net (code "88") (name "unconnected-(U5-CTS-Pad11)") (class "Default")
      (node (ref "U5") (pin "11") (pinfunction "CTS_11") (pintype "input"))
    )
    (net (code "89") (name "unconnected-(U5-DCD-Pad10)") (class "Default")
      (node (ref "U5") (pin "10") (pinfunction "DCD_10") (pintype "input"))
    )
    (net (code "90") (name "unconnected-(U5-DSR-Pad9)") (class "Default")
      (node (ref "U5") (pin "9") (pinfunction "DSR_9") (pintype "input"))
    )
    (net (code "91") (name "unconnected-(U5-OSCI-Pad27)") (class "Default")
      (node (ref "U5") (pin "27") (pinfunction "OSCI_27") (pintype "input"))
    )
    (net (code "92") (name "unconnected-(U5-OSCO-Pad28)") (class "Default")
      (node (ref "U5") (pin "28") (pinfunction "OSCO_28") (pintype "output"))
    )
    (net (code "93") (name "unconnected-(U5-PWREN-Pad14)") (class "Default")
      (node (ref "U5") (pin "14") (pinfunction "PWREN_14") (pintype "input"))
    )
    (net (code "94") (name "unconnected-(U5-RESET-Pad19)") (class "Default")
      (node (ref "U5") (pin "19") (pinfunction "RESET_19") (pintype "input"))
    )
    (net (code "95") (name "unconnected-(U5-RI-Pad6)") (class "Default")
      (node (ref "U5") (pin "6") (pinfunction "RI_6") (pintype "input"))
    )
    (net (code "96") (name "unconnected-(U5-RTS-Pad3)") (class "Default")
      (node (ref "U5") (pin "3") (pinfunction "RTS_3") (pintype "output"))
    )
    (net (code "97") (name "unconnected-(U5-SLEEP-Pad12)") (class "Default")
      (node (ref "U5") (pin "12") (pinfunction "SLEEP_12") (pintype "input"))
    )
    (net (code "98") (name "unconnected-(U5-TXDEN-Pad13)") (class "Default")
      (node (ref "U5") (pin "13") (pinfunction "TXDEN_13") (pintype "input"))
    )
  )
)
